# BO.net
KiCad netlist of a schematic drawn in EAGLE
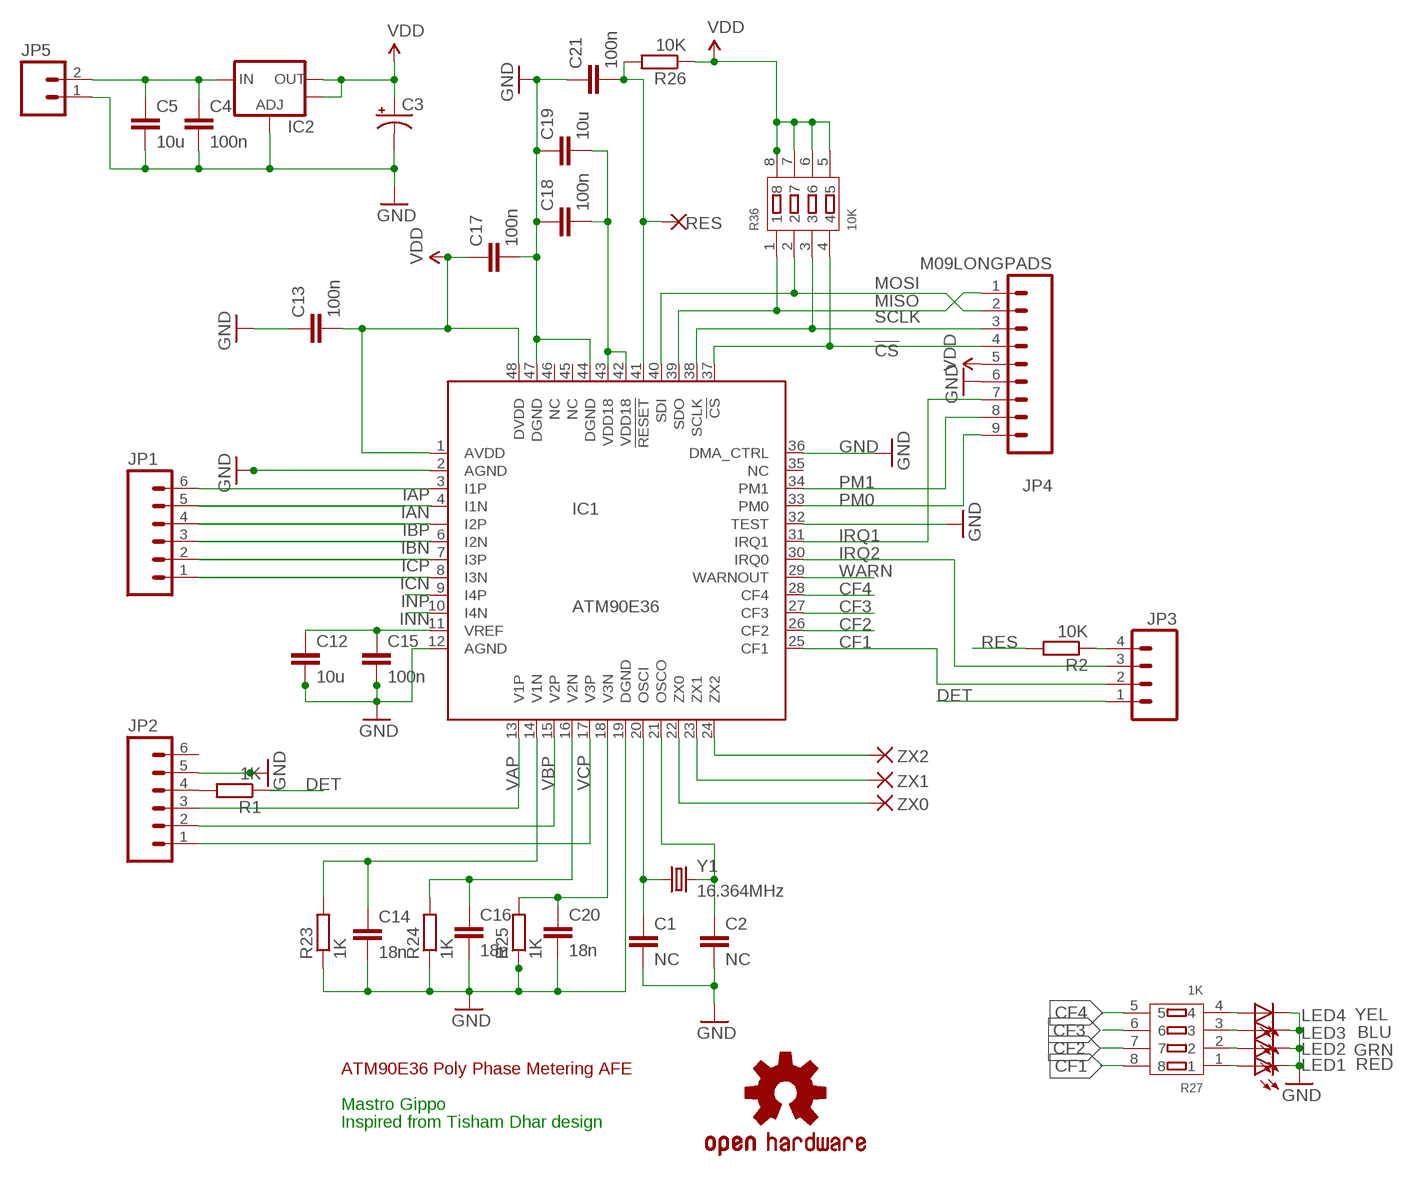
[diagram p0: schematic, sheet 1]

(export (version "E")
  (design (tool "Eeschema 10.0.6"))
  (components
    (comp (ref "C1")
      (value "NC")
      (footprint "eagle-import:C0805K")
      (libsource (lib "eagle-import") (part "C-EUC0805K"))
    )
    (comp (ref "C2")
      (value "NC")
      (footprint "eagle-import:C0805K")
      (libsource (lib "eagle-import") (part "C-EUC0805K"))
    )
    (comp (ref "C3")
      (value "CPOL-USE5-6")
      (footprint "eagle-import:E5-6")
      (libsource (lib "eagle-import") (part "CPOL-USE5-6"))
    )
    (comp (ref "C4")
      (value "100n")
      (footprint "eagle-import:C0805K")
      (libsource (lib "eagle-import") (part "C-EUC0805K"))
    )
    (comp (ref "C5")
      (value "10u")
      (footprint "eagle-import:C0805K")
      (libsource (lib "eagle-import") (part "C-EUC0805K"))
    )
    (comp (ref "C12")
      (value "10u")
      (footprint "eagle-import:C0805K")
      (libsource (lib "eagle-import") (part "C-EUC0805K"))
    )
    (comp (ref "C13")
      (value "100n")
      (footprint "eagle-import:C0805K")
      (libsource (lib "eagle-import") (part "C-EUC0805K"))
    )
    (comp (ref "C14")
      (value "18n")
      (footprint "eagle-import:C0805K")
      (libsource (lib "eagle-import") (part "C-EUC0805K"))
    )
    (comp (ref "C15")
      (value "100n")
      (footprint "eagle-import:C0805K")
      (libsource (lib "eagle-import") (part "C-EUC0805K"))
    )
    (comp (ref "C16")
      (value "18n")
      (footprint "eagle-import:C0805K")
      (libsource (lib "eagle-import") (part "C-EUC0805K"))
    )
    (comp (ref "C17")
      (value "100n")
      (footprint "eagle-import:C0805K")
      (libsource (lib "eagle-import") (part "C-EUC0805K"))
    )
    (comp (ref "C18")
      (value "100n")
      (footprint "eagle-import:C0805K")
      (libsource (lib "eagle-import") (part "C-EUC0805K"))
    )
    (comp (ref "C19")
      (value "10u")
      (footprint "eagle-import:C0805K")
      (libsource (lib "eagle-import") (part "C-EUC0805K"))
    )
    (comp (ref "C20")
      (value "18n")
      (footprint "eagle-import:C0805K")
      (libsource (lib "eagle-import") (part "C-EUC0805K"))
    )
    (comp (ref "C21")
      (value "100n")
      (footprint "eagle-import:C0805K")
      (libsource (lib "eagle-import") (part "C-EUC0805K"))
    )
    (comp (ref "IC1")
      (value "ATM90E36")
      (footprint "eagle-import:TQFP48")
      (libsource (lib "eagle-import") (part "ATM90E36"))
    )
    (comp (ref "IC2")
      (value "V_REG_LM1117SOT223")
      (footprint "eagle-import:SOT223")
      (libsource (lib "eagle-import") (part "V_REG_LM1117SOT223"))
    )
    (comp (ref "JP1")
      (value "M06LONGPADS")
      (footprint "eagle-import:1X06_LONGPADS")
      (libsource (lib "eagle-import") (part "M06LONGPADS"))
    )
    (comp (ref "JP2")
      (value "M06LONGPADS")
      (footprint "eagle-import:1X06_LONGPADS")
      (libsource (lib "eagle-import") (part "M06LONGPADS"))
    )
    (comp (ref "JP3")
      (value "M04LONGPADS")
      (footprint "eagle-import:1X04_LONGPADS")
      (libsource (lib "eagle-import") (part "M04LONGPADS"))
    )
    (comp (ref "JP4")
      (value "M09LONGPADS")
      (footprint "eagle-import:1X09_LONGPADS")
      (libsource (lib "eagle-import") (part "M09LONGPADS"))
    )
    (comp (ref "JP5")
      (value "M02PTH3")
      (footprint "eagle-import:1X02_LONGPADS")
      (libsource (lib "eagle-import") (part "M02PTH3"))
    )
    (comp (ref "LED1")
      (value "RED")
      (footprint "eagle-import:CHIP-LED0603")
      (libsource (lib "eagle-import") (part "LEDCHIP-LED0603"))
    )
    (comp (ref "LED2")
      (value "GRN")
      (footprint "eagle-import:CHIP-LED0603")
      (libsource (lib "eagle-import") (part "LEDCHIP-LED0603"))
    )
    (comp (ref "LED3")
      (value "BLU")
      (footprint "eagle-import:CHIP-LED0603")
      (libsource (lib "eagle-import") (part "LEDCHIP-LED0603"))
    )
    (comp (ref "LED4")
      (value "YEL")
      (footprint "eagle-import:CHIP-LED0603")
      (libsource (lib "eagle-import") (part "LEDCHIP-LED0603"))
    )
    (comp (ref "LOGO1")
      (value "OSHW-LOGOM")
      (footprint "eagle-import:OSHW-LOGO-M")
      (libsource (lib "eagle-import") (part "OSHW-LOGOM"))
    )
    (comp (ref "R1")
      (value "1K")
      (footprint "eagle-import:M0805")
      (libsource (lib "eagle-import") (part "R-EU_M0805"))
    )
    (comp (ref "R2")
      (value "10K")
      (footprint "eagle-import:M0805")
      (libsource (lib "eagle-import") (part "R-EU_M0805"))
    )
    (comp (ref "R23")
      (value "1K")
      (footprint "eagle-import:M0805")
      (libsource (lib "eagle-import") (part "R-EU_M0805"))
    )
    (comp (ref "R24")
      (value "1K")
      (footprint "eagle-import:M0805")
      (libsource (lib "eagle-import") (part "R-EU_M0805"))
    )
    (comp (ref "R25")
      (value "1K")
      (footprint "eagle-import:M0805")
      (libsource (lib "eagle-import") (part "R-EU_M0805"))
    )
    (comp (ref "R26")
      (value "10K")
      (footprint "eagle-import:M0805")
      (libsource (lib "eagle-import") (part "R-EU_M0805"))
    )
    (comp (ref "R27")
      (value "1K")
      (footprint "eagle-import:RA1206-8")
      (fields (field (name "MPN") "Chip-Array-Series-1%"))
      (libsource (lib "eagle-import") (part "SMD-RES-ARRAY-1K-4R(RA1206-8)"))
    )
    (comp (ref "R36")
      (value "10K")
      (footprint "eagle-import:RA1206-8")
      (fields (field (name "MPN") "Chip-Array-Series-1%"))
      (libsource (lib "eagle-import") (part "SMD-RES-ARRAY-1K-4R(RA1206-8)"))
    )
    (comp (ref "RES")
      (value "ZX0")
      (footprint "eagle-import:SMD1,27-2,54")
      (libsource (lib "eagle-import") (part "SMD2"))
    )
    (comp (ref "Y1")
      (value "16.364MHz")
      (footprint "eagle-import:HC49UP")
      (libsource (lib "eagle-import") (part "CRYSTALSMD"))
    )
    (comp (ref "ZX0")
      (value "ZX0")
      (footprint "eagle-import:SMD1,27-2,54")
      (libsource (lib "eagle-import") (part "SMD2"))
    )
    (comp (ref "ZX1")
      (value "ZX1")
      (footprint "eagle-import:SMD1,27-2,54")
      (libsource (lib "eagle-import") (part "SMD2"))
    )
    (comp (ref "ZX2")
      (value "ZX0")
      (footprint "eagle-import:SMD1,27-2,54")
      (libsource (lib "eagle-import") (part "SMD2"))
    )
  )
  (nets
    (net (code "1") (name "/DET") (class "Default")
      (node (ref "JP3") (pin "1") (pinfunction "1_1") (pintype "passive"))
      (node (ref "R1") (pin "1") (pinfunction "1_1") (pintype "passive"))
    )
    (net (code "2") (name "/IAN") (class "Default")
      (node (ref "IC1") (pin "4") (pinfunction "I1N_4") (pintype "input"))
      (node (ref "JP1") (pin "5") (pinfunction "5_5") (pintype "passive"))
    )
    (net (code "3") (name "/IAP") (class "Default")
      (node (ref "IC1") (pin "3") (pinfunction "I1P_3") (pintype "input"))
      (node (ref "JP1") (pin "6") (pinfunction "6_6") (pintype "passive"))
    )
    (net (code "4") (name "/IBN") (class "Default")
      (node (ref "IC1") (pin "6") (pinfunction "I2N_6") (pintype "input"))
      (node (ref "JP1") (pin "3") (pinfunction "3_3") (pintype "passive"))
    )
    (net (code "5") (name "/IBP") (class "Default")
      (node (ref "IC1") (pin "5") (pinfunction "I2P_5") (pintype "input"))
      (node (ref "JP1") (pin "4") (pinfunction "4_4") (pintype "passive"))
    )
    (net (code "6") (name "/ICN") (class "Default")
      (node (ref "IC1") (pin "8") (pinfunction "I3N_8") (pintype "input"))
      (node (ref "JP1") (pin "1") (pinfunction "1_1") (pintype "passive"))
    )
    (net (code "7") (name "/ICP") (class "Default")
      (node (ref "IC1") (pin "7") (pinfunction "I3P_7") (pintype "input"))
      (node (ref "JP1") (pin "2") (pinfunction "2_2") (pintype "passive"))
    )
    (net (code "8") (name "/INN") (class "Default")
      (node (ref "IC1") (pin "10") (pinfunction "I4N_10") (pintype "input"))
    )
    (net (code "9") (name "/INP") (class "Default")
      (node (ref "IC1") (pin "9") (pinfunction "I4P_9") (pintype "input"))
    )
    (net (code "10") (name "/IRQ1") (class "Default")
      (node (ref "IC1") (pin "31") (pinfunction "IRQ1_31") (pintype "output"))
      (node (ref "JP4") (pin "7") (pinfunction "7_7") (pintype "passive"))
    )
    (net (code "11") (name "/IRQ2") (class "Default")
      (node (ref "IC1") (pin "30") (pinfunction "IRQ0_30") (pintype "output"))
      (node (ref "JP3") (pin "3") (pinfunction "3_3") (pintype "passive"))
    )
    (net (code "12") (name "/MISO") (class "Default")
      (node (ref "IC1") (pin "39") (pinfunction "SDO_39") (pintype "output"))
      (node (ref "JP4") (pin "1") (pinfunction "1_1") (pintype "passive"))
      (node (ref "R36") (pin "1") (pinfunction "1_1") (pintype "bidirectional"))
    )
    (net (code "13") (name "/MOSI") (class "Default")
      (node (ref "IC1") (pin "40") (pinfunction "SDI_40") (pintype "input"))
      (node (ref "JP4") (pin "2") (pinfunction "2_2") (pintype "passive"))
      (node (ref "R36") (pin "2") (pinfunction "2_2") (pintype "bidirectional"))
    )
    (net (code "14") (name "/PM0") (class "Default")
      (node (ref "IC1") (pin "33") (pinfunction "PM0_33") (pintype "input"))
      (node (ref "JP4") (pin "9") (pinfunction "9_9") (pintype "passive"))
    )
    (net (code "15") (name "/PM1") (class "Default")
      (node (ref "IC1") (pin "34") (pinfunction "PM1_34") (pintype "input"))
      (node (ref "JP4") (pin "8") (pinfunction "8_8") (pintype "passive"))
    )
    (net (code "16") (name "/RES") (class "Default")
      (node (ref "C21") (pin "2") (pinfunction "2_2") (pintype "passive"))
      (node (ref "IC1") (pin "41") (pinfunction "~{RESET}_41") (pintype "input"))
      (node (ref "R2") (pin "2") (pinfunction "2_2") (pintype "passive"))
      (node (ref "R26") (pin "2") (pinfunction "2_2") (pintype "passive"))
      (node (ref "RES") (pin "1") (pinfunction "P_1") (pintype "passive"))
    )
    (net (code "17") (name "/SCLK") (class "Default")
      (node (ref "IC1") (pin "38") (pinfunction "SCLK_38") (pintype "input"))
      (node (ref "JP4") (pin "3") (pinfunction "3_3") (pintype "passive"))
      (node (ref "R36") (pin "3") (pinfunction "3_3") (pintype "bidirectional"))
    )
    (net (code "18") (name "/VAP") (class "Default")
      (node (ref "IC1") (pin "13") (pinfunction "V1P_13") (pintype "input"))
      (node (ref "JP2") (pin "3") (pinfunction "3_3") (pintype "passive"))
    )
    (net (code "19") (name "/VBP") (class "Default")
      (node (ref "IC1") (pin "15") (pinfunction "V2P_15") (pintype "input"))
      (node (ref "JP2") (pin "2") (pinfunction "2_2") (pintype "passive"))
    )
    (net (code "20") (name "/VCP") (class "Default")
      (node (ref "IC1") (pin "17") (pinfunction "V3P_17") (pintype "input"))
      (node (ref "JP2") (pin "1") (pinfunction "1_1") (pintype "passive"))
    )
    (net (code "21") (name "/WARN") (class "Default")
      (node (ref "IC1") (pin "29") (pinfunction "WARNOUT_29") (pintype "output"))
    )
    (net (code "22") (name "/~{CS}") (class "Default")
      (node (ref "IC1") (pin "37") (pinfunction "~{CS}_37") (pintype "input"))
      (node (ref "JP4") (pin "4") (pinfunction "4_4") (pintype "passive"))
      (node (ref "R36") (pin "4") (pinfunction "4_4") (pintype "bidirectional"))
    )
    (net (code "23") (name "CF1") (class "Default")
      (node (ref "IC1") (pin "25") (pinfunction "CF1_25") (pintype "output"))
      (node (ref "JP3") (pin "2") (pinfunction "2_2") (pintype "passive"))
      (node (ref "R27") (pin "8") (pinfunction "8_8") (pintype "bidirectional"))
    )
    (net (code "24") (name "CF2") (class "Default")
      (node (ref "IC1") (pin "26") (pinfunction "CF2_26") (pintype "output"))
      (node (ref "R27") (pin "7") (pinfunction "7_7") (pintype "bidirectional"))
    )
    (net (code "25") (name "CF3") (class "Default")
      (node (ref "IC1") (pin "27") (pinfunction "CF3_27") (pintype "output"))
      (node (ref "R27") (pin "6") (pinfunction "6_6") (pintype "bidirectional"))
    )
    (net (code "26") (name "CF4") (class "Default")
      (node (ref "IC1") (pin "28") (pinfunction "CF4_28") (pintype "output"))
      (node (ref "R27") (pin "5") (pinfunction "5_5") (pintype "bidirectional"))
    )
    (net (code "27") (name "GND") (class "Default")
      (node (ref "C1") (pin "2") (pinfunction "2_2") (pintype "passive"))
      (node (ref "C12") (pin "2") (pinfunction "2_2") (pintype "passive"))
      (node (ref "C13") (pin "1") (pinfunction "1_1") (pintype "passive"))
      (node (ref "C14") (pin "2") (pinfunction "2_2") (pintype "passive"))
      (node (ref "C15") (pin "2") (pinfunction "2_2") (pintype "passive"))
      (node (ref "C16") (pin "2") (pinfunction "2_2") (pintype "passive"))
      (node (ref "C17") (pin "2") (pinfunction "2_2") (pintype "passive"))
      (node (ref "C18") (pin "1") (pinfunction "1_1") (pintype "passive"))
      (node (ref "C19") (pin "1") (pinfunction "1_1") (pintype "passive"))
      (node (ref "C2") (pin "2") (pinfunction "2_2") (pintype "passive"))
      (node (ref "C20") (pin "2") (pinfunction "2_2") (pintype "passive"))
      (node (ref "C21") (pin "1") (pinfunction "1_1") (pintype "passive"))
      (node (ref "C3") (pin "-") (pinfunction "-_-") (pintype "passive"))
      (node (ref "C4") (pin "2") (pinfunction "2_2") (pintype "passive"))
      (node (ref "C5") (pin "2") (pinfunction "2_2") (pintype "passive"))
      (node (ref "IC1") (pin "12") (pinfunction "AGND_12") (pintype "power_in"))
      (node (ref "IC1") (pin "19") (pinfunction "DGND_19") (pintype "power_in"))
      (node (ref "IC1") (pin "2") (pinfunction "AGND_2") (pintype "power_in"))
      (node (ref "IC1") (pin "32") (pinfunction "TEST_32") (pintype "power_in"))
      (node (ref "IC1") (pin "36") (pinfunction "DMA_CTRL_36") (pintype "input"))
      (node (ref "IC1") (pin "44") (pinfunction "DGND_44") (pintype "power_in"))
      (node (ref "IC1") (pin "47") (pinfunction "DGND_47") (pintype "power_in"))
      (node (ref "IC2") (pin "1") (pinfunction "ADJ_1") (pintype "input"))
      (node (ref "JP2") (pin "5") (pinfunction "5_5") (pintype "passive"))
      (node (ref "JP4") (pin "6") (pinfunction "6_6") (pintype "passive"))
      (node (ref "JP5") (pin "1") (pinfunction "1_1") (pintype "passive"))
      (node (ref "LED1") (pin "C") (pinfunction "C_C") (pintype "passive"))
      (node (ref "LED2") (pin "C") (pinfunction "C_C") (pintype "passive"))
      (node (ref "LED3") (pin "C") (pinfunction "C_C") (pintype "passive"))
      (node (ref "LED4") (pin "C") (pinfunction "C_C") (pintype "passive"))
      (node (ref "R23") (pin "1") (pinfunction "1_1") (pintype "passive"))
      (node (ref "R24") (pin "1") (pinfunction "1_1") (pintype "passive"))
      (node (ref "R25") (pin "1") (pinfunction "1_1") (pintype "passive"))
    )
    (net (code "28") (name "Net-(C18-Pad2)") (class "Default")
      (node (ref "C18") (pin "2") (pinfunction "2_2") (pintype "passive"))
      (node (ref "C19") (pin "2") (pinfunction "2_2") (pintype "passive"))
      (node (ref "IC1") (pin "42") (pinfunction "VDD18_42") (pintype "power_in"))
      (node (ref "IC1") (pin "43") (pinfunction "VDD18_43") (pintype "power_in"))
    )
    (net (code "29") (name "Net-(IC1-OSCI)") (class "Default")
      (node (ref "C1") (pin "1") (pinfunction "1_1") (pintype "passive"))
      (node (ref "IC1") (pin "20") (pinfunction "OSCI_20") (pintype "input"))
      (node (ref "Y1") (pin "1") (pinfunction "1_1") (pintype "passive"))
    )
    (net (code "30") (name "Net-(IC1-OSCO)") (class "Default")
      (node (ref "C2") (pin "1") (pinfunction "1_1") (pintype "passive"))
      (node (ref "IC1") (pin "21") (pinfunction "OSCO_21") (pintype "output"))
      (node (ref "Y1") (pin "2") (pinfunction "2_2") (pintype "passive"))
    )
    (net (code "31") (name "Net-(IC1-V1N)") (class "Default")
      (node (ref "C14") (pin "1") (pinfunction "1_1") (pintype "passive"))
      (node (ref "IC1") (pin "14") (pinfunction "V1N_14") (pintype "input"))
      (node (ref "R23") (pin "2") (pinfunction "2_2") (pintype "passive"))
    )
    (net (code "32") (name "Net-(IC1-V2N)") (class "Default")
      (node (ref "C16") (pin "1") (pinfunction "1_1") (pintype "passive"))
      (node (ref "IC1") (pin "16") (pinfunction "V2N_16") (pintype "input"))
      (node (ref "R24") (pin "2") (pinfunction "2_2") (pintype "passive"))
    )
    (net (code "33") (name "Net-(IC1-V3N)") (class "Default")
      (node (ref "C20") (pin "1") (pinfunction "1_1") (pintype "passive"))
      (node (ref "IC1") (pin "18") (pinfunction "V3N_18") (pintype "input"))
      (node (ref "R25") (pin "2") (pinfunction "2_2") (pintype "passive"))
    )
    (net (code "34") (name "Net-(IC1-VREF)") (class "Default")
      (node (ref "C12") (pin "1") (pinfunction "1_1") (pintype "passive"))
      (node (ref "C15") (pin "1") (pinfunction "1_1") (pintype "passive"))
      (node (ref "IC1") (pin "11") (pinfunction "VREF_11") (pintype "bidirectional"))
    )
    (net (code "35") (name "Net-(IC1-ZX0)") (class "Default")
      (node (ref "IC1") (pin "22") (pinfunction "ZX0_22") (pintype "output"))
      (node (ref "ZX0") (pin "1") (pinfunction "P_1") (pintype "passive"))
    )
    (net (code "36") (name "Net-(IC1-ZX1)") (class "Default")
      (node (ref "IC1") (pin "23") (pinfunction "ZX1_23") (pintype "output"))
      (node (ref "ZX1") (pin "1") (pinfunction "P_1") (pintype "passive"))
    )
    (net (code "37") (name "Net-(IC1-ZX2)") (class "Default")
      (node (ref "IC1") (pin "24") (pinfunction "ZX2_24") (pintype "output"))
      (node (ref "ZX2") (pin "1") (pinfunction "P_1") (pintype "passive"))
    )
    (net (code "38") (name "Net-(IC2-IN)") (class "Default")
      (node (ref "C4") (pin "1") (pinfunction "1_1") (pintype "passive"))
      (node (ref "C5") (pin "1") (pinfunction "1_1") (pintype "passive"))
      (node (ref "IC2") (pin "3") (pinfunction "IN_3") (pintype "input"))
      (node (ref "JP5") (pin "2") (pinfunction "2_2") (pintype "passive"))
    )
    (net (code "39") (name "Net-(JP2-Pad4)") (class "Default")
      (node (ref "JP2") (pin "4") (pinfunction "4_4") (pintype "passive"))
      (node (ref "R1") (pin "2") (pinfunction "2_2") (pintype "passive"))
    )
    (net (code "40") (name "Net-(JP3-Pad4)") (class "Default")
      (node (ref "JP3") (pin "4") (pinfunction "4_4") (pintype "passive"))
      (node (ref "R2") (pin "1") (pinfunction "1_1") (pintype "passive"))
    )
    (net (code "41") (name "Net-(LED1-PadA)") (class "Default")
      (node (ref "LED1") (pin "A") (pinfunction "A_A") (pintype "passive"))
      (node (ref "R27") (pin "1") (pinfunction "1_1") (pintype "bidirectional"))
    )
    (net (code "42") (name "Net-(LED2-PadA)") (class "Default")
      (node (ref "LED2") (pin "A") (pinfunction "A_A") (pintype "passive"))
      (node (ref "R27") (pin "2") (pinfunction "2_2") (pintype "bidirectional"))
    )
    (net (code "43") (name "Net-(LED3-PadA)") (class "Default")
      (node (ref "LED3") (pin "A") (pinfunction "A_A") (pintype "passive"))
      (node (ref "R27") (pin "3") (pinfunction "3_3") (pintype "bidirectional"))
    )
    (net (code "44") (name "Net-(LED4-PadA)") (class "Default")
      (node (ref "LED4") (pin "A") (pinfunction "A_A") (pintype "passive"))
      (node (ref "R27") (pin "4") (pinfunction "4_4") (pintype "bidirectional"))
    )
    (net (code "45") (name "VDD") (class "Default")
      (node (ref "C13") (pin "2") (pinfunction "2_2") (pintype "passive"))
      (node (ref "C17") (pin "1") (pinfunction "1_1") (pintype "passive"))
      (node (ref "C3") (pin "+") (pinfunction "+_+") (pintype "passive"))
      (node (ref "IC1") (pin "1") (pinfunction "AVDD_1") (pintype "power_in"))
      (node (ref "IC1") (pin "48") (pinfunction "DVDD_48") (pintype "power_in"))
      (node (ref "IC2") (pin "2") (pinfunction "OUT_2") (pintype "output"))
      (node (ref "IC2") (pin "4") (pinfunction "OUT_4") (pintype "output"))
      (node (ref "JP4") (pin "5") (pinfunction "5_5") (pintype "passive"))
      (node (ref "R26") (pin "1") (pinfunction "1_1") (pintype "passive"))
      (node (ref "R36") (pin "5") (pinfunction "5_5") (pintype "bidirectional"))
      (node (ref "R36") (pin "6") (pinfunction "6_6") (pintype "bidirectional"))
      (node (ref "R36") (pin "7") (pinfunction "7_7") (pintype "bidirectional"))
      (node (ref "R36") (pin "8") (pinfunction "8_8") (pintype "bidirectional"))
    )
    (net (code "46") (name "unconnected-(IC1-NC-Pad35)") (class "Default")
      (node (ref "IC1") (pin "35") (pinfunction "NC_35") (pintype "no_connect"))
    )
    (net (code "47") (name "unconnected-(IC1-NC-Pad45)") (class "Default")
      (node (ref "IC1") (pin "45") (pinfunction "NC_45") (pintype "no_connect"))
    )
    (net (code "48") (name "unconnected-(IC1-NC-Pad46)") (class "Default")
      (node (ref "IC1") (pin "46") (pinfunction "NC_46") (pintype "no_connect"))
    )
    (net (code "49") (name "unconnected-(JP2-Pad6)") (class "Default")
      (node (ref "JP2") (pin "6") (pinfunction "6_6") (pintype "passive"))
    )
  )
)
